# Sensors.net
KiCad netlist of a schematic drawn in Altium Designer
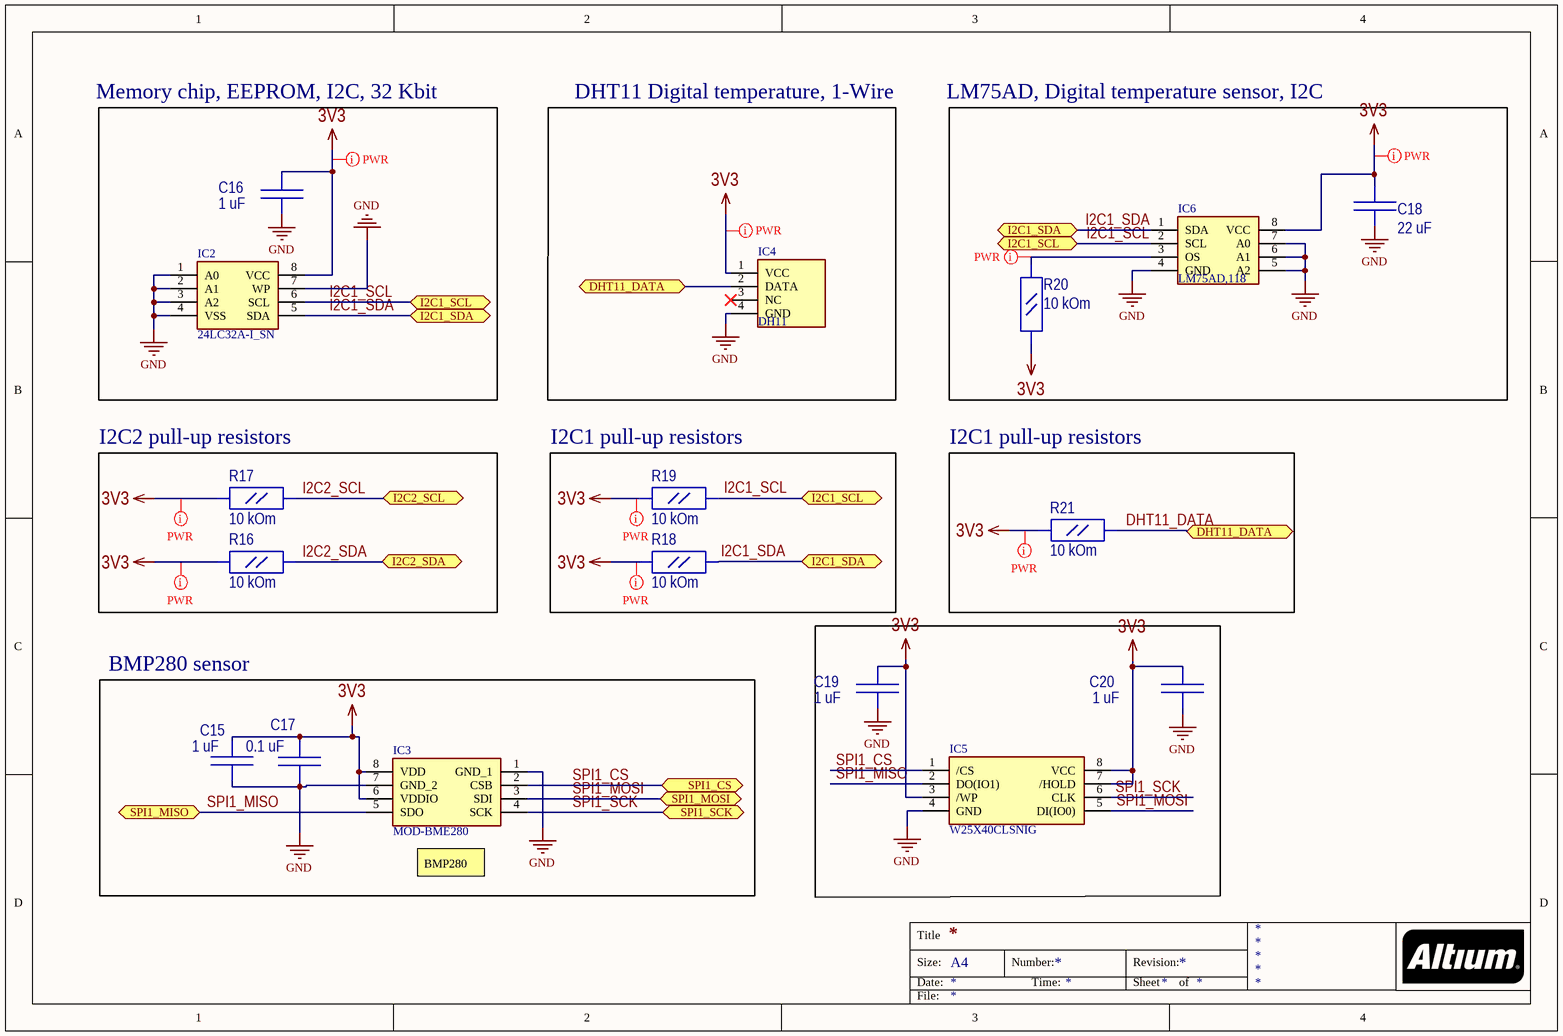
[diagram p0: Sensors.SchDoc]

(export (version "E")
  (design (tool "Eeschema 10.0.6"))
  (components
    (comp (ref "C15") (value "1 uF") (footprint "C_0805") (libsource (lib "2.Capasitors") (part "C_0805")))
    (comp (ref "C16") (value "1 uF") (footprint "C_0805") (libsource (lib "2.Capasitors") (part "C_0805")))
    (comp (ref "C17") (value "0.1 uF") (footprint "C_0805") (libsource (lib "2.Capasitors") (part "C_0805")))
    (comp (ref "C18") (value "22 uF") (footprint "C_0805") (libsource (lib "2.Capasitors") (part "C_0805")))
    (comp (ref "C19") (value "1 uF") (footprint "C_0805") (libsource (lib "2.Capasitors") (part "C_0805")))
    (comp (ref "C20") (value "1 uF") (footprint "C_0805") (libsource (lib "2.Capasitors") (part "C_0805")))
    (comp (ref "IC2")
      (value "24LC32A-I_SN")
      (footprint "SamacSys:SOIC127P600X175-8N")
      (description "Integrated Circuit")
      (fields
        (field (name "MANUFACTURER_PART_NUMBER") "24LC32A-I/SN")
        (field (name "MOUSER PART NUMBER") "579-24LC32A-I/SN")
      )
      (libsource (lib "*") (part "24LC32A-I_SN"))
    )
    (comp (ref "IC3")
      (value "MOD-BME280")
      (footprint "SamacSys:MODBME280")
      (description "Integrated Circuit")
      (fields (field (name "MOUSER PART NUMBER") "909-MOD-BME280"))
      (libsource (lib "*") (part "MOD-BME280"))
    )
    (comp (ref "IC4")
      (value "DH11")
      (footprint "SamacSys:HDRV4W80P0X254_1X4_1200X500X1550P")
      (description "Integrated Circuit")
      (fields
        (field (name "MANUFACTURER_PART_NUMBER") "101020011")
        (field (name "MOUSER PART NUMBER") "713-101020011")
      )
      (libsource (lib "*") (part "101020011"))
    )
    (comp (ref "IC5")
      (value "W25X40CLSNIG")
      (footprint "SamacSys:SOIC127P600X175-8N")
      (description "Integrated Circuit")
      (fields (field (name "MOUSER PART NUMBER") "454-W25X40CLSNIG"))
      (libsource (lib "*") (part "W25X40CLSNIG"))
    )
    (comp (ref "IC6")
      (value "LM75AD,118")
      (footprint "SamacSys:SOIC127P600X175-8N")
      (description "Integrated Circuit")
      (fields (field (name "MOUSER PART NUMBER") "771-LM75AD-T"))
      (libsource (lib "*") (part "LM75AD,118"))
    )
    (comp (ref "R16") (value "10 kOm") (footprint "R_0805") (libsource (lib "1.Resistors") (part "R_0805")))
    (comp (ref "R17") (value "10 kOm") (footprint "R_0805") (libsource (lib "1.Resistors") (part "R_0805")))
    (comp (ref "R18") (value "10 kOm") (footprint "R_0805") (libsource (lib "1.Resistors") (part "R_0805")))
    (comp (ref "R19") (value "10 kOm") (footprint "R_0805") (libsource (lib "1.Resistors") (part "R_0805")))
    (comp (ref "R20") (value "10 kOm") (footprint "R_0805") (libsource (lib "1.Resistors") (part "R_0805")))
    (comp (ref "R21") (value "10 kOm") (footprint "R_0805") (libsource (lib "1.Resistors") (part "R_0805")))
  )
  (nets
    (net (code "1") (name "/DHT11_DATA") (class "Default")
      (node (ref "IC4") (pin "2") (pinfunction "DATA_2") (pintype "passive"))
      (node (ref "R21") (pin "2") (pinfunction "2_2") (pintype "passive"))
    )
    (net (code "2") (name "/I2C1_SCL") (class "Default")
      (node (ref "IC2") (pin "6") (pinfunction "SCL_6") (pintype "passive"))
      (node (ref "IC6") (pin "2") (pinfunction "SCL_2") (pintype "passive"))
      (node (ref "R19") (pin "2") (pinfunction "2_2") (pintype "passive"))
    )
    (net (code "3") (name "/I2C1_SDA") (class "Default")
      (node (ref "IC2") (pin "5") (pinfunction "SDA_5") (pintype "passive"))
      (node (ref "IC6") (pin "1") (pinfunction "SDA_1") (pintype "passive"))
      (node (ref "R18") (pin "2") (pinfunction "2_2") (pintype "passive"))
    )
    (net (code "4") (name "/I2C2_SCL") (class "Default")
      (node (ref "R17") (pin "2") (pinfunction "2_2") (pintype "passive"))
    )
    (net (code "5") (name "/I2C2_SDA") (class "Default")
      (node (ref "R16") (pin "2") (pinfunction "2_2") (pintype "passive"))
    )
    (net (code "6") (name "/SPI1_CS") (class "Default")
      (node (ref "IC3") (pin "2") (pinfunction "CSB_2") (pintype "passive"))
      (node (ref "IC5") (pin "1") (pinfunction "/CS_1") (pintype "passive"))
    )
    (net (code "7") (name "/SPI1_MISO") (class "Default")
      (node (ref "IC3") (pin "5") (pinfunction "SDO_5") (pintype "passive"))
      (node (ref "IC5") (pin "2") (pinfunction "DO(IO1)_2") (pintype "passive"))
    )
    (net (code "8") (name "/SPI1_MOSI") (class "Default")
      (node (ref "IC3") (pin "3") (pinfunction "SDI_3") (pintype "passive"))
      (node (ref "IC5") (pin "5") (pinfunction "DI(IO0)_5") (pintype "passive"))
    )
    (net (code "9") (name "/SPI1_SCK") (class "Default")
      (node (ref "IC3") (pin "4") (pinfunction "SCK_4") (pintype "passive"))
      (node (ref "IC5") (pin "6") (pinfunction "CLK_6") (pintype "passive"))
    )
    (net (code "10") (name "3V3") (class "Default")
      (node (ref "C15") (pin "2") (pinfunction "2_2") (pintype "passive"))
      (node (ref "C16") (pin "2") (pinfunction "2_2") (pintype "passive"))
      (node (ref "C17") (pin "2") (pinfunction "2_2") (pintype "passive"))
      (node (ref "C18") (pin "2") (pinfunction "2_2") (pintype "passive"))
      (node (ref "C19") (pin "2") (pinfunction "2_2") (pintype "passive"))
      (node (ref "C20") (pin "2") (pinfunction "2_2") (pintype "passive"))
      (node (ref "IC2") (pin "8") (pinfunction "VCC_8") (pintype "passive"))
      (node (ref "IC3") (pin "6") (pinfunction "VDDIO_6") (pintype "passive"))
      (node (ref "IC3") (pin "8") (pinfunction "VDD_8") (pintype "passive"))
      (node (ref "IC4") (pin "1") (pinfunction "VCC_1") (pintype "passive"))
      (node (ref "IC5") (pin "3") (pinfunction "/WP_3") (pintype "passive"))
      (node (ref "IC5") (pin "7") (pinfunction "/HOLD_7") (pintype "passive"))
      (node (ref "IC5") (pin "8") (pinfunction "VCC_8") (pintype "passive"))
      (node (ref "IC6") (pin "8") (pinfunction "VCC_8") (pintype "passive"))
      (node (ref "R16") (pin "1") (pinfunction "1_1") (pintype "passive"))
      (node (ref "R17") (pin "1") (pinfunction "1_1") (pintype "passive"))
      (node (ref "R18") (pin "1") (pinfunction "1_1") (pintype "passive"))
      (node (ref "R19") (pin "1") (pinfunction "1_1") (pintype "passive"))
      (node (ref "R20") (pin "1") (pinfunction "1_1") (pintype "passive"))
      (node (ref "R21") (pin "1") (pinfunction "1_1") (pintype "passive"))
    )
    (net (code "11") (name "GND") (class "Default")
      (node (ref "C15") (pin "1") (pinfunction "1_1") (pintype "passive"))
      (node (ref "C16") (pin "1") (pinfunction "1_1") (pintype "passive"))
      (node (ref "C17") (pin "1") (pinfunction "1_1") (pintype "passive"))
      (node (ref "C18") (pin "1") (pinfunction "1_1") (pintype "passive"))
      (node (ref "C19") (pin "1") (pinfunction "1_1") (pintype "passive"))
      (node (ref "C20") (pin "1") (pinfunction "1_1") (pintype "passive"))
      (node (ref "IC2") (pin "1") (pinfunction "A0_1") (pintype "passive"))
      (node (ref "IC2") (pin "2") (pinfunction "A1_2") (pintype "passive"))
      (node (ref "IC2") (pin "3") (pinfunction "A2_3") (pintype "passive"))
      (node (ref "IC2") (pin "4") (pinfunction "VSS_4") (pintype "passive"))
      (node (ref "IC2") (pin "7") (pinfunction "WP_7") (pintype "passive"))
      (node (ref "IC3") (pin "1") (pinfunction "GND_1_1") (pintype "passive"))
      (node (ref "IC3") (pin "7") (pinfunction "GND_2_7") (pintype "passive"))
      (node (ref "IC4") (pin "4") (pinfunction "GND_4") (pintype "passive"))
      (node (ref "IC5") (pin "4") (pinfunction "GND_4") (pintype "passive"))
      (node (ref "IC6") (pin "4") (pinfunction "GND_4") (pintype "passive"))
      (node (ref "IC6") (pin "5") (pinfunction "A2_5") (pintype "passive"))
      (node (ref "IC6") (pin "6") (pinfunction "A1_6") (pintype "passive"))
      (node (ref "IC6") (pin "7") (pinfunction "A0_7") (pintype "passive"))
    )
    (net (code "12") (name "Net-(IC6-OS)") (class "Default")
      (node (ref "IC6") (pin "3") (pinfunction "OS_3") (pintype "passive"))
      (node (ref "R20") (pin "2") (pinfunction "2_2") (pintype "passive"))
    )
    (net (code "13") (name "unconnected-(IC4-NC-Pad3)") (class "Default")
      (node (ref "IC4") (pin "3") (pinfunction "NC_3") (pintype "passive+no_connect"))
    )
  )
)
